# BasicPeripherals.net
KiCad netlist of a schematic drawn in Altium Designer
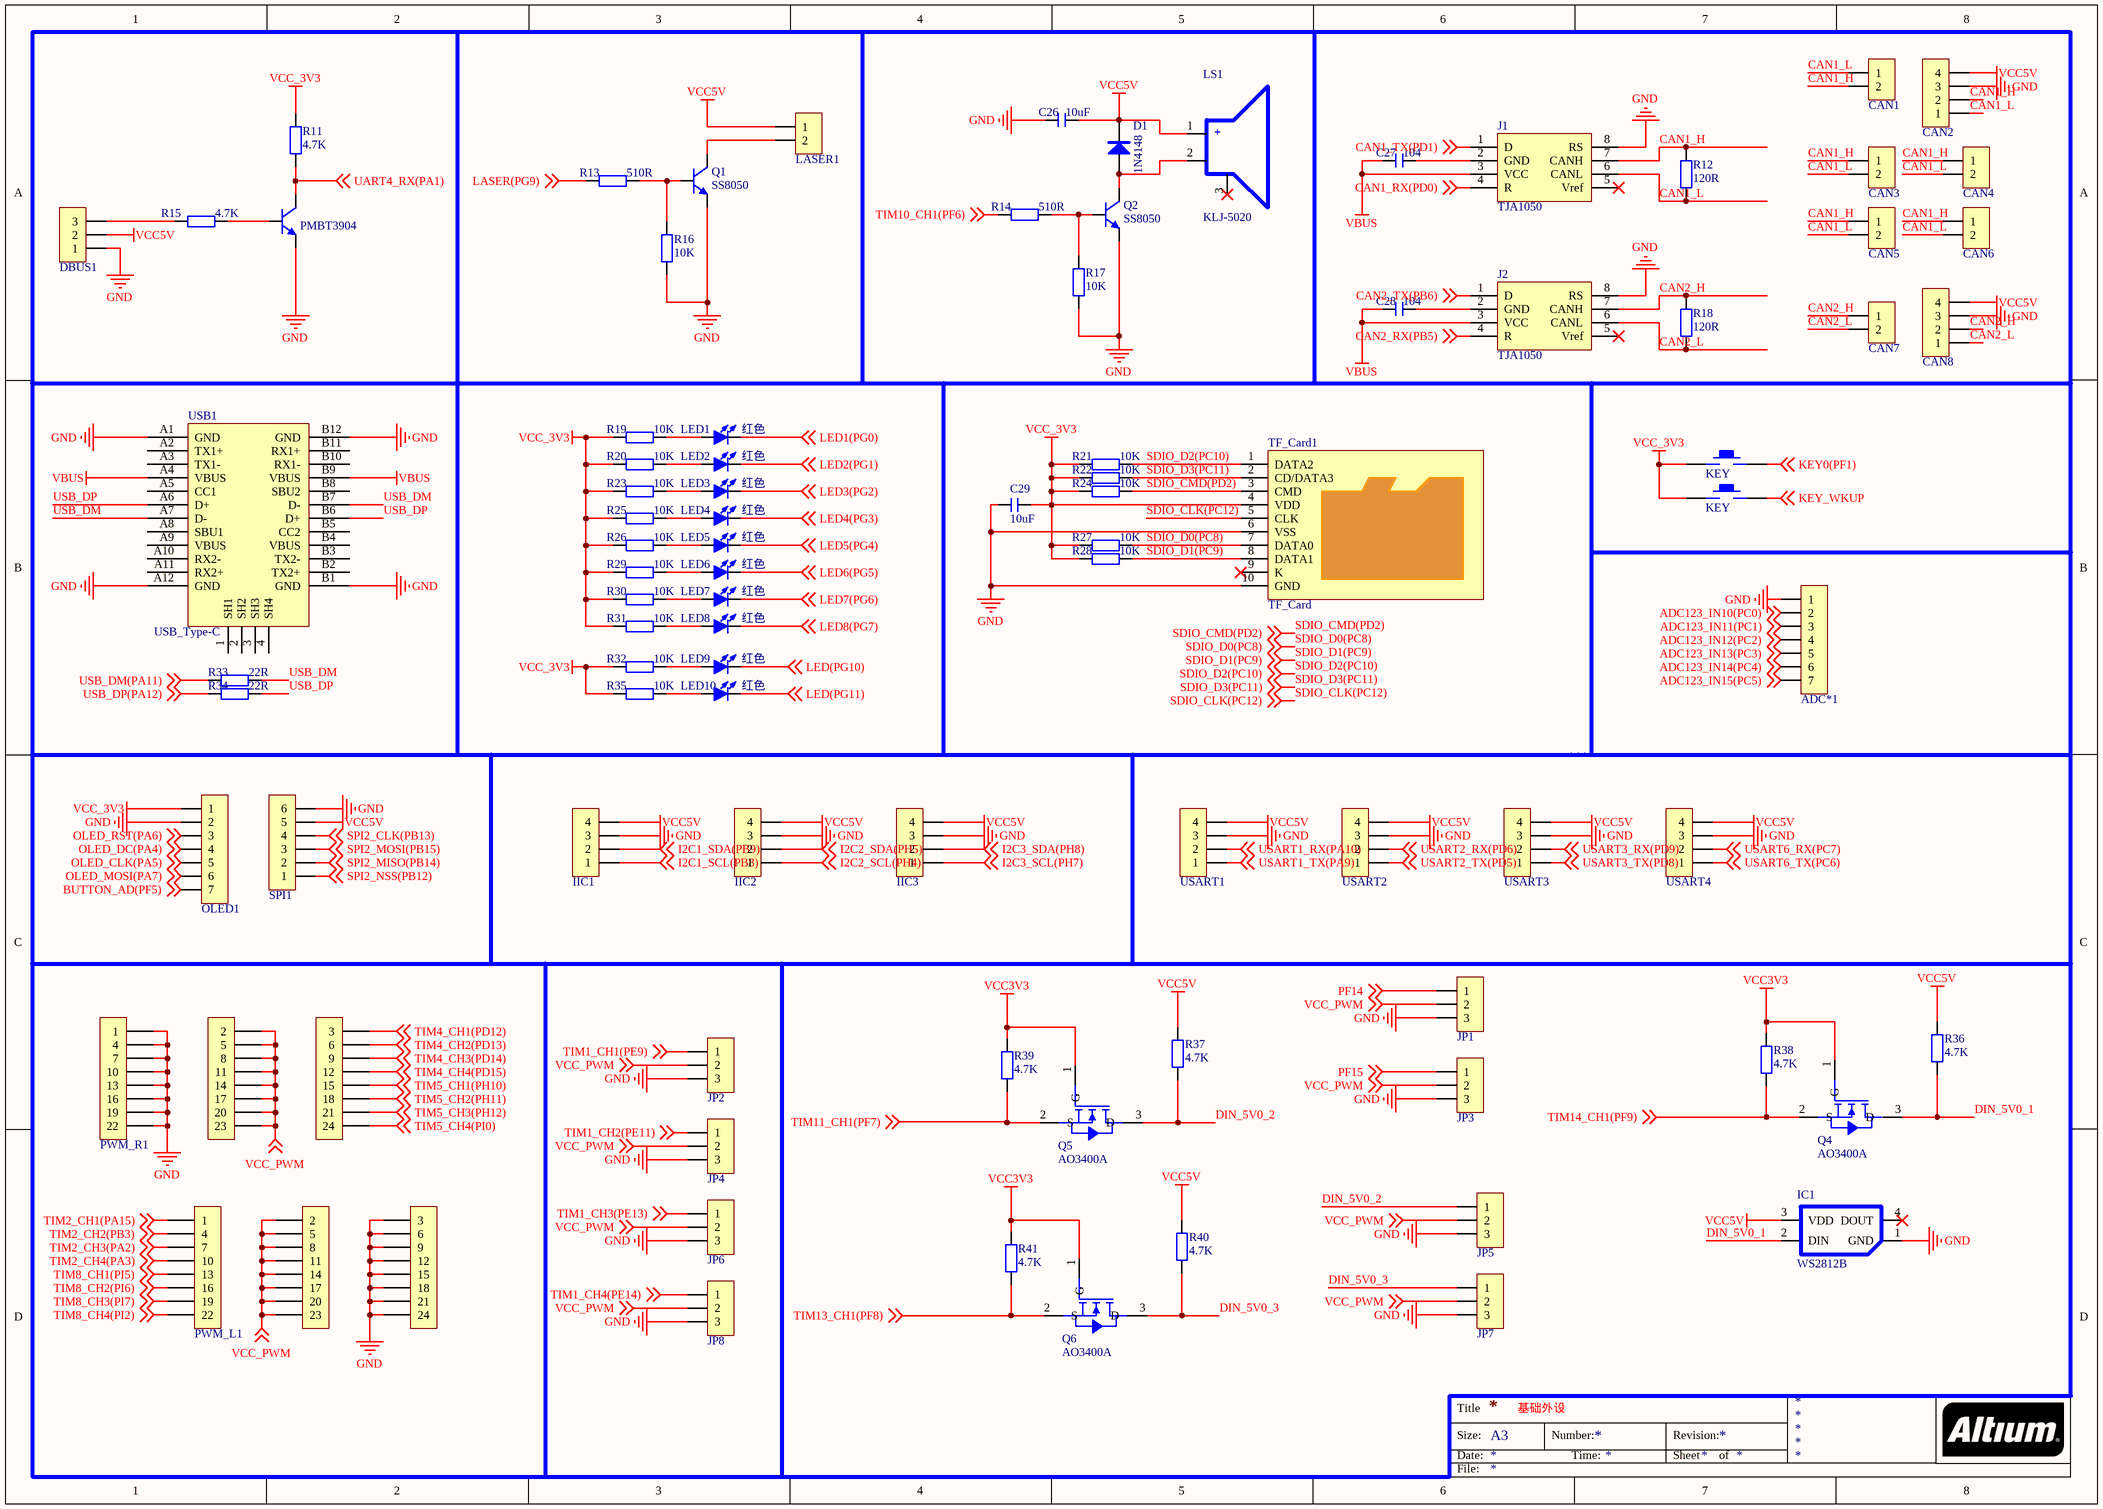
[diagram p0: BasicPeripherals.SchDoc]

(export (version "E")
  (design (tool "Eeschema 10.0.6"))
  (components
    (comp (ref "ADC*1")
      (value "HDR-1X7")
      (footprint "MX 1.25-WS-7P")
      (description "7P接插件")
      (libsource (lib "5.0 - 接插件-脚距1.25") (part "Header 7"))
    )
    (comp (ref "C26")
      (value "10uF")
      (footprint "C 0402_M")
      (description "贴片电容")
      (libsource (lib "0.1 - 电阻-电容-电感") (part "C"))
    )
    (comp (ref "C27")
      (value "104")
      (footprint "C 0603_L")
      (description "贴片电容")
      (libsource (lib "0.1 - 电阻-电容-电感") (part "C"))
    )
    (comp (ref "C28")
      (value "104")
      (footprint "C 0603_L")
      (description "贴片电容")
      (libsource (lib "0.1 - 电阻-电容-电感") (part "C"))
    )
    (comp (ref "C29")
      (value "10uF")
      (footprint "C 0402_M")
      (description "贴片电容")
      (libsource (lib "0.1 - 电阻-电容-电感") (part "C"))
    )
    (comp (ref "CAN1")
      (value "HDR-1X2")
      (footprint "MX 1.25-WS-2P")
      (description "2P接插件")
      (libsource (lib "5.0 - 接插件-脚距1.25") (part "Header 2"))
    )
    (comp (ref "CAN2")
      (value "HDR-1X4")
      (footprint "MX 1.25-WS-4P")
      (description "4P接插件")
      (libsource (lib "5.0 - 接插件-脚距1.25") (part "Header 4"))
    )
    (comp (ref "CAN3")
      (value "HDR-1X2")
      (footprint "MX 1.25-LS-2P")
      (description "2P接插件")
      (libsource (lib "5.0 - 接插件-脚距1.25") (part "Header 2"))
    )
    (comp (ref "CAN4")
      (value "HDR-1X2")
      (footprint "MX 1.25-LS-2P")
      (description "2P接插件")
      (libsource (lib "5.0 - 接插件-脚距1.25") (part "Header 2"))
    )
    (comp (ref "CAN5")
      (value "HDR-1X2")
      (footprint "MX 1.25-LS-2P")
      (description "2P接插件")
      (libsource (lib "5.0 - 接插件-脚距1.25") (part "Header 2"))
    )
    (comp (ref "CAN6")
      (value "HDR-1X2")
      (footprint "MX 1.25-LS-2P")
      (description "2P接插件")
      (libsource (lib "5.0 - 接插件-脚距1.25") (part "Header 2"))
    )
    (comp (ref "CAN7")
      (value "HDR-1X2")
      (footprint "MX 1.25-LS-2P")
      (description "2P接插件")
      (libsource (lib "5.0 - 接插件-脚距1.25") (part "Header 2"))
    )
    (comp (ref "CAN8")
      (value "HDR-1X4")
      (footprint "MX 1.25-LS-4P")
      (description "4P接插件")
      (libsource (lib "5.0 - 接插件-脚距1.25") (part "Header 4"))
    )
    (comp (ref "D1")
      (value "1N4148")
      (footprint "SOD-323")
      (description "开关二极管")
      (libsource (lib "0.2 -  二极管-整流桥") (part "1N4148"))
    )
    (comp (ref "DBUS1")
      (value "HDR-1X3")
      (footprint "HDR2.54-WS-3P")
      (description "3P接插件")
      (libsource (lib "") (part "Header 3_1"))
    )
    (comp (ref "IC1")
      (value "WS2812B")
      (footprint "LED 3528-4Pin")
      (libsource (lib "mx_pcb_library") (part "WS2812B"))
    )
    (comp (ref "IIC1")
      (value "HDR-1X4")
      (footprint "MX 1.25-LS-4P")
      (description "4P接插件")
      (libsource (lib "5.0 - 接插件-脚距1.25") (part "Header 4"))
    )
    (comp (ref "IIC2")
      (value "HDR-1X4")
      (footprint "MX 1.25-LS-4P")
      (description "4P接插件")
      (libsource (lib "5.0 - 接插件-脚距1.25") (part "Header 4"))
    )
    (comp (ref "IIC3")
      (value "HDR-1X4")
      (footprint "MX 1.25-LS-4P")
      (description "4P接插件")
      (libsource (lib "5.0 - 接插件-脚距1.25") (part "Header 4"))
    )
    (comp (ref "J1")
      (value "TJA1050")
      (footprint "mx_pcb_library:SOIC-8_150mil")
      (description "CAN芯片")
      (libsource (lib "mx_pcb_library") (part "TJA1050"))
    )
    (comp (ref "J2")
      (value "TJA1050")
      (footprint "mx_pcb_library:SOIC-8_150mil")
      (description "CAN芯片")
      (libsource (lib "mx_pcb_library") (part "TJA1050"))
    )
    (comp (ref "JP1")
      (value "HDR-1X3")
      (footprint "HDR2.54-LI-3P")
      (description "3P接插件")
      (libsource (lib "5.3 - 接插件-脚距2.54 (100mil) ") (part "Header 3"))
    )
    (comp (ref "JP2")
      (value "HDR-1X3")
      (footprint "HDR2.54-LI-3P")
      (description "3P接插件")
      (libsource (lib "5.3 - 接插件-脚距2.54 (100mil) ") (part "Header 3"))
    )
    (comp (ref "JP3")
      (value "HDR-1X3")
      (footprint "HDR2.54-LI-3P")
      (description "3P接插件")
      (libsource (lib "5.3 - 接插件-脚距2.54 (100mil) ") (part "Header 3"))
    )
    (comp (ref "JP4")
      (value "HDR-1X3")
      (footprint "HDR2.54-LI-3P")
      (description "3P接插件")
      (libsource (lib "5.3 - 接插件-脚距2.54 (100mil) ") (part "Header 3"))
    )
    (comp (ref "JP5")
      (value "HDR-1X3")
      (footprint "HDR2.54-LI-3P")
      (description "3P接插件")
      (libsource (lib "5.3 - 接插件-脚距2.54 (100mil) ") (part "Header 3"))
    )
    (comp (ref "JP6")
      (value "HDR-1X3")
      (footprint "HDR2.54-LI-3P")
      (description "3P接插件")
      (libsource (lib "5.3 - 接插件-脚距2.54 (100mil) ") (part "Header 3"))
    )
    (comp (ref "JP7")
      (value "HDR-1X3")
      (footprint "HDR2.54-LI-3P")
      (description "3P接插件")
      (libsource (lib "5.3 - 接插件-脚距2.54 (100mil) ") (part "Header 3"))
    )
    (comp (ref "JP8")
      (value "HDR-1X3")
      (footprint "HDR2.54-LI-3P")
      (description "3P接插件")
      (libsource (lib "5.3 - 接插件-脚距2.54 (100mil) ") (part "Header 3"))
    )
    (comp (ref "LASER1")
      (value "HDR-1X2")
      (footprint "MX 1.25-LS-2P")
      (description "2P接插件")
      (libsource (lib "5.0 - 接插件-脚距1.25") (part "Header 2"))
    )
    (comp (ref "LED1")
      (value "红色")
      (footprint "LED 0805G")
      (description "贴片LED")
      (libsource (lib "0.3 - LED发光二极管") (part "LED-SMD"))
    )
    (comp (ref "LED2")
      (value "红色")
      (footprint "LED 0805G")
      (description "贴片LED")
      (libsource (lib "0.3 - LED发光二极管") (part "LED-SMD"))
    )
    (comp (ref "LED3")
      (value "红色")
      (footprint "LED 0805G")
      (description "贴片LED")
      (libsource (lib "0.3 - LED发光二极管") (part "LED-SMD"))
    )
    (comp (ref "LED4")
      (value "红色")
      (footprint "LED 0805G")
      (description "贴片LED")
      (libsource (lib "0.3 - LED发光二极管") (part "LED-SMD"))
    )
    (comp (ref "LED5")
      (value "红色")
      (footprint "LED 0805G")
      (description "贴片LED")
      (libsource (lib "0.3 - LED发光二极管") (part "LED-SMD"))
    )
    (comp (ref "LED6")
      (value "红色")
      (footprint "LED 0805G")
      (description "贴片LED")
      (libsource (lib "0.3 - LED发光二极管") (part "LED-SMD"))
    )
    (comp (ref "LED7")
      (value "红色")
      (footprint "LED 0805G")
      (description "贴片LED")
      (libsource (lib "0.3 - LED发光二极管") (part "LED-SMD"))
    )
    (comp (ref "LED8")
      (value "红色")
      (footprint "LED 0805G")
      (description "贴片LED")
      (libsource (lib "0.3 - LED发光二极管") (part "LED-SMD"))
    )
    (comp (ref "LED9")
      (value "红色")
      (footprint "LED 0805R")
      (description "贴片LED")
      (libsource (lib "0.3 - LED发光二极管") (part "LED-SMD"))
    )
    (comp (ref "LED10")
      (value "红色")
      (footprint "LED 0805R")
      (description "贴片LED")
      (libsource (lib "0.3 - LED发光二极管") (part "LED-SMD"))
    )
    (comp (ref "LS1")
      (value "KLJ-5020")
      (footprint "mx_pcb_library:BUZ-SMD_4P-L5.0-W5.0-P3.80-TL")
      (description "蜂鸣器")
      (libsource (lib "mx_pcb_library") (part "KLJ-5020"))
    )
    (comp (ref "OLED1")
      (value "HDR-1X7")
      (footprint "MX 1.25-WS-7P")
      (description "7P接插件")
      (libsource (lib "5.0 - 接插件-脚距1.25") (part "Header 7"))
    )
    (comp (ref "PWM_L1")
      (value "HDR3*8-left")
      (footprint "mx_pcb_library:PIN-3*8-2.54 - duplicate")
      (description "Connector")
      (libsource (lib "mx_pcb_library") (part "HDR3*8-left"))
    )
    (comp (ref "PWM_R1")
      (value "HDR3*8-right")
      (footprint "mx_pcb_library:PIN-3*8-2.54 - duplicate")
      (description "Connector")
      (libsource (lib "mx_pcb_library") (part "HDR3*8-right"))
    )
    (comp (ref "Q1")
      (value "SS8050")
      (footprint "SOT23-3L")
      (description "高频放大-NPN型")
      (libsource (lib "0.4 - 三极管") (part "8050-SMD"))
    )
    (comp (ref "Q2")
      (value "SS8050")
      (footprint "SOT23-3L")
      (description "高频放大-NPN型")
      (libsource (lib "0.4 - 三极管") (part "8050-SMD"))
    )
    (comp (ref "Q3")
      (value "PMBT3904")
      (footprint "mx_pcb_library:SOT-23-3")
      (description "NPN Bipolar Transistor")
      (libsource (lib "mx_pcb_library") (part "PMBT3904"))
    )
    (comp (ref "Q4")
      (value "AO3400A")
      (footprint "mx_pcb_library:SOT-23-3_L2.9-W1.3-P1.90-LS2.4-BR")
      (libsource (lib "mx_pcb_library") (part "AO3400A"))
    )
    (comp (ref "Q5")
      (value "AO3400A")
      (footprint "mx_pcb_library:SOT-23-3_L2.9-W1.3-P1.90-LS2.4-BR")
      (libsource (lib "mx_pcb_library") (part "AO3400A"))
    )
    (comp (ref "Q6")
      (value "AO3400A")
      (footprint "mx_pcb_library:SOT-23-3_L2.9-W1.3-P1.90-LS2.4-BR")
      (libsource (lib "mx_pcb_library") (part "AO3400A"))
    )
    (comp (ref "R11")
      (value "4.7K")
      (footprint "R 0402_M")
      (description "贴片电阻")
      (libsource (lib "0.1 - 电阻-电容-电感") (part "R"))
    )
    (comp (ref "R12")
      (value "120R")
      (footprint "R 0402_M")
      (description "贴片电阻")
      (libsource (lib "0.1 - 电阻-电容-电感") (part "R"))
    )
    (comp (ref "R13")
      (value "510R")
      (footprint "R 0402_M")
      (description "贴片电阻")
      (libsource (lib "0.1 - 电阻-电容-电感") (part "R"))
    )
    (comp (ref "R14")
      (value "510R")
      (footprint "R 0402_M")
      (description "贴片电阻")
      (libsource (lib "0.1 - 电阻-电容-电感") (part "R"))
    )
    (comp (ref "R15")
      (value "4.7K")
      (footprint "R 0402_M")
      (description "贴片电阻")
      (libsource (lib "0.1 - 电阻-电容-电感") (part "R"))
    )
    (comp (ref "R16")
      (value "10K")
      (footprint "R 0402_M")
      (description "贴片电阻")
      (libsource (lib "0.1 - 电阻-电容-电感") (part "R"))
    )
    (comp (ref "R17")
      (value "10K")
      (footprint "R 0402_M")
      (description "贴片电阻")
      (libsource (lib "0.1 - 电阻-电容-电感") (part "R"))
    )
    (comp (ref "R18")
      (value "120R")
      (footprint "R 0402_M")
      (description "贴片电阻")
      (libsource (lib "0.1 - 电阻-电容-电感") (part "R"))
    )
    (comp (ref "R19")
      (value "10K")
      (footprint "R 0402_M")
      (description "贴片电阻")
      (libsource (lib "0.1 - 电阻-电容-电感") (part "R"))
    )
    (comp (ref "R20")
      (value "10K")
      (footprint "R 0402_M")
      (description "贴片电阻")
      (libsource (lib "0.1 - 电阻-电容-电感") (part "R"))
    )
    (comp (ref "R21")
      (value "10K")
      (footprint "R 0402_M")
      (description "贴片电阻")
      (libsource (lib "0.1 - 电阻-电容-电感") (part "R"))
    )
    (comp (ref "R22")
      (value "10K")
      (footprint "R 0402_M")
      (description "贴片电阻")
      (libsource (lib "0.1 - 电阻-电容-电感") (part "R"))
    )
    (comp (ref "R23")
      (value "10K")
      (footprint "R 0402_M")
      (description "贴片电阻")
      (libsource (lib "0.1 - 电阻-电容-电感") (part "R"))
    )
    (comp (ref "R24")
      (value "10K")
      (footprint "R 0402_M")
      (description "贴片电阻")
      (libsource (lib "0.1 - 电阻-电容-电感") (part "R"))
    )
    (comp (ref "R25")
      (value "10K")
      (footprint "R 0402_M")
      (description "贴片电阻")
      (libsource (lib "0.1 - 电阻-电容-电感") (part "R"))
    )
    (comp (ref "R26")
      (value "10K")
      (footprint "R 0402_M")
      (description "贴片电阻")
      (libsource (lib "0.1 - 电阻-电容-电感") (part "R"))
    )
    (comp (ref "R27")
      (value "10K")
      (footprint "R 0402_M")
      (description "贴片电阻")
      (libsource (lib "0.1 - 电阻-电容-电感") (part "R"))
    )
    (comp (ref "R28")
      (value "10K")
      (footprint "R 0402_M")
      (description "贴片电阻")
      (libsource (lib "0.1 - 电阻-电容-电感") (part "R"))
    )
    (comp (ref "R29")
      (value "10K")
      (footprint "R 0402_M")
      (description "贴片电阻")
      (libsource (lib "0.1 - 电阻-电容-电感") (part "R"))
    )
    (comp (ref "R30")
      (value "10K")
      (footprint "R 0402_M")
      (description "贴片电阻")
      (libsource (lib "0.1 - 电阻-电容-电感") (part "R"))
    )
    (comp (ref "R31")
      (value "10K")
      (footprint "R 0402_M")
      (description "贴片电阻")
      (libsource (lib "0.1 - 电阻-电容-电感") (part "R"))
    )
    (comp (ref "R32")
      (value "10K")
      (footprint "R 0402_M")
      (description "贴片电阻")
      (libsource (lib "0.1 - 电阻-电容-电感") (part "R"))
    )
    (comp (ref "R33")
      (value "22R")
      (footprint "R 0402_M")
      (description "贴片电阻")
      (libsource (lib "0.1 - 电阻-电容-电感") (part "R"))
    )
    (comp (ref "R34")
      (value "22R")
      (footprint "R 0402_M")
      (description "贴片电阻")
      (libsource (lib "0.1 - 电阻-电容-电感") (part "R"))
    )
    (comp (ref "R35")
      (value "10K")
      (footprint "R 0402_M")
      (description "贴片电阻")
      (libsource (lib "0.1 - 电阻-电容-电感") (part "R"))
    )
    (comp (ref "R36")
      (value "4.7K")
      (footprint "R 0402_M")
      (description "贴片电阻")
      (libsource (lib "0.1 - 电阻-电容-电感") (part "R"))
    )
    (comp (ref "R37")
      (value "4.7K")
      (footprint "R 0402_M")
      (description "贴片电阻")
      (libsource (lib "0.1 - 电阻-电容-电感") (part "R"))
    )
    (comp (ref "R38")
      (value "4.7K")
      (footprint "R 0402_M")
      (description "贴片电阻")
      (libsource (lib "0.1 - 电阻-电容-电感") (part "R"))
    )
    (comp (ref "R39")
      (value "4.7K")
      (footprint "R 0402_M")
      (description "贴片电阻")
      (libsource (lib "0.1 - 电阻-电容-电感") (part "R"))
    )
    (comp (ref "R40")
      (value "4.7K")
      (footprint "R 0402_M")
      (description "贴片电阻")
      (libsource (lib "0.1 - 电阻-电容-电感") (part "R"))
    )
    (comp (ref "R41")
      (value "4.7K")
      (footprint "R 0402_M")
      (description "贴片电阻")
      (libsource (lib "0.1 - 电阻-电容-电感") (part "R"))
    )
    (comp (ref "RST2")
      (value "KEY")
      (footprint "mx_pcb_library:SMD-3.2*4.2")
      (libsource (lib "mx_pcb_library") (part "KEY_M"))
    )
    (comp (ref "RST3")
      (value "KEY")
      (footprint "mx_pcb_library:SMD-3.2*4.2")
      (libsource (lib "mx_pcb_library") (part "KEY_M"))
    )
    (comp (ref "SPI1")
      (value "HDR-1X6")
      (footprint "MX 1.25-LS-6P")
      (description "6P接插件")
      (libsource (lib "5.0 - 接插件-脚距1.25") (part "Header 6"))
    )
    (comp (ref "TF_Card1")
      (value "TF_Card")
      (footprint "Micro SD")
      (description "TF卡座")
      (libsource (lib "0.8 - 网口-音频插座") (part "TF_Card"))
    )
    (comp (ref "USART1")
      (value "HDR-1X4")
      (footprint "MX 1.25-LS-4P")
      (description "4P接插件")
      (libsource (lib "5.0 - 接插件-脚距1.25") (part "Header 4"))
    )
    (comp (ref "USART2")
      (value "HDR-1X4")
      (footprint "MX 1.25-LS-4P")
      (description "4P接插件")
      (libsource (lib "5.0 - 接插件-脚距1.25") (part "Header 4"))
    )
    (comp (ref "USART3")
      (value "HDR-1X4")
      (footprint "MX 1.25-LS-4P")
      (description "4P接插件")
      (libsource (lib "5.0 - 接插件-脚距1.25") (part "Header 4"))
    )
    (comp (ref "USART4")
      (value "HDR-1X4")
      (footprint "MX 1.25-LS-4P")
      (description "4P接插件")
      (libsource (lib "5.0 - 接插件-脚距1.25") (part "Header 4"))
    )
    (comp (ref "USB1")
      (value "USB_Type-C")
      (footprint "mx_pcb_library:Type-C-TOP")
      (libsource (lib "mx_pcb_library") (part "USB_Type-C"))
    )
  )
  (nets
    (net (code "1") (name "/CAN1_H") (class "Default")
      (node (ref "CAN1") (pin "2") (pinfunction "2_2") (pintype "passive"))
      (node (ref "CAN2") (pin "2") (pinfunction "2_2") (pintype "passive"))
      (node (ref "CAN3") (pin "1") (pinfunction "1_1") (pintype "passive"))
      (node (ref "CAN4") (pin "1") (pinfunction "1_1") (pintype "passive"))
      (node (ref "CAN5") (pin "1") (pinfunction "1_1") (pintype "passive"))
      (node (ref "CAN6") (pin "1") (pinfunction "1_1") (pintype "passive"))
      (node (ref "J1") (pin "7") (pinfunction "CANH_7") (pintype "passive"))
      (node (ref "R12") (pin "2") (pinfunction "2_2") (pintype "passive"))
    )
    (net (code "2") (name "/CAN1_L") (class "Default")
      (node (ref "CAN1") (pin "1") (pinfunction "1_1") (pintype "passive"))
      (node (ref "CAN2") (pin "1") (pinfunction "1_1") (pintype "passive"))
      (node (ref "CAN3") (pin "2") (pinfunction "2_2") (pintype "passive"))
      (node (ref "CAN4") (pin "2") (pinfunction "2_2") (pintype "passive"))
      (node (ref "CAN5") (pin "2") (pinfunction "2_2") (pintype "passive"))
      (node (ref "CAN6") (pin "2") (pinfunction "2_2") (pintype "passive"))
      (node (ref "J1") (pin "6") (pinfunction "CANL_6") (pintype "passive"))
      (node (ref "R12") (pin "1") (pinfunction "1_1") (pintype "passive"))
    )
    (net (code "3") (name "/CAN2_H") (class "Default")
      (node (ref "CAN7") (pin "1") (pinfunction "1_1") (pintype "passive"))
      (node (ref "CAN8") (pin "2") (pinfunction "2_2") (pintype "passive"))
      (node (ref "J2") (pin "7") (pinfunction "CANH_7") (pintype "passive"))
      (node (ref "R18") (pin "2") (pinfunction "2_2") (pintype "passive"))
    )
    (net (code "4") (name "/CAN2_L") (class "Default")
      (node (ref "CAN7") (pin "2") (pinfunction "2_2") (pintype "passive"))
      (node (ref "CAN8") (pin "1") (pinfunction "1_1") (pintype "passive"))
      (node (ref "J2") (pin "6") (pinfunction "CANL_6") (pintype "passive"))
      (node (ref "R18") (pin "1") (pinfunction "1_1") (pintype "passive"))
    )
    (net (code "5") (name "/DIN_5V0_1") (class "Default")
      (node (ref "IC1") (pin "2") (pinfunction "DIN_2") (pintype "passive"))
      (node (ref "Q4") (pin "3") (pinfunction "D_3") (pintype "passive"))
      (node (ref "R36") (pin "2") (pinfunction "2_2") (pintype "passive"))
    )
    (net (code "6") (name "/DIN_5V0_2") (class "Default")
      (node (ref "JP5") (pin "1") (pinfunction "1_1") (pintype "passive"))
      (node (ref "Q5") (pin "3") (pinfunction "D_3") (pintype "passive"))
      (node (ref "R37") (pin "2") (pinfunction "2_2") (pintype "passive"))
    )
    (net (code "7") (name "/DIN_5V0_3") (class "Default")
      (node (ref "JP7") (pin "1") (pinfunction "1_1") (pintype "passive"))
      (node (ref "Q6") (pin "3") (pinfunction "D_3") (pintype "passive"))
      (node (ref "R40") (pin "2") (pinfunction "2_2") (pintype "passive"))
    )
    (net (code "8") (name "/USB_DM") (class "Default")
      (node (ref "R33") (pin "2") (pinfunction "2_2") (pintype "passive"))
      (node (ref "USB1") (pin "A7") (pinfunction "D-_A7") (pintype "passive"))
      (node (ref "USB1") (pin "B7") (pinfunction "D-_B7") (pintype "passive"))
    )
    (net (code "9") (name "/USB_DP") (class "Default")
      (node (ref "R34") (pin "2") (pinfunction "2_2") (pintype "passive"))
      (node (ref "USB1") (pin "A6") (pinfunction "D+_A6") (pintype "passive"))
      (node (ref "USB1") (pin "B6") (pinfunction "D+_B6") (pintype "passive"))
    )
    (net (code "10") (name "ADC123_IN10(PC0)") (class "Default")
      (node (ref "ADC*1") (pin "2") (pinfunction "2_2") (pintype "passive"))
    )
    (net (code "11") (name "ADC123_IN11(PC1)") (class "Default")
      (node (ref "ADC*1") (pin "3") (pinfunction "3_3") (pintype "passive"))
    )
    (net (code "12") (name "ADC123_IN12(PC2)") (class "Default")
      (node (ref "ADC*1") (pin "4") (pinfunction "4_4") (pintype "passive"))
    )
    (net (code "13") (name "ADC123_IN13(PC3)") (class "Default")
      (node (ref "ADC*1") (pin "5") (pinfunction "5_5") (pintype "passive"))
    )
    (net (code "14") (name "ADC123_IN14(PC4)") (class "Default")
      (node (ref "ADC*1") (pin "6") (pinfunction "6_6") (pintype "passive"))
    )
    (net (code "15") (name "ADC123_IN15(PC5)") (class "Default")
      (node (ref "ADC*1") (pin "7") (pinfunction "7_7") (pintype "passive"))
    )
    (net (code "16") (name "BUTTON_AD(PF5)") (class "Default")
      (node (ref "OLED1") (pin "7") (pinfunction "7_7") (pintype "passive"))
    )
    (net (code "17") (name "CAN1_RX(PD0)") (class "Default")
      (node (ref "J1") (pin "4") (pinfunction "R_4") (pintype "passive"))
    )
    (net (code "18") (name "CAN1_TX(PD1)") (class "Default")
      (node (ref "J1") (pin "1") (pinfunction "D_1") (pintype "passive"))
    )
    (net (code "19") (name "CAN2_RX(PB5)") (class "Default")
      (node (ref "J2") (pin "4") (pinfunction "R_4") (pintype "passive"))
    )
    (net (code "20") (name "CAN2_TX(PB6)") (class "Default")
      (node (ref "J2") (pin "1") (pinfunction "D_1") (pintype "passive"))
    )
    (net (code "21") (name "GND") (class "Default")
      (node (ref "ADC*1") (pin "1") (pinfunction "1_1") (pintype "passive"))
      (node (ref "C26") (pin "2") (pinfunction "2_2") (pintype "passive"))
      (node (ref "C29") (pin "1") (pinfunction "1_1") (pintype "passive"))
      (node (ref "CAN2") (pin "3") (pinfunction "3_3") (pintype "passive"))
      (node (ref "CAN8") (pin "3") (pinfunction "3_3") (pintype "passive"))
      (node (ref "DBUS1") (pin "1") (pinfunction "1_1") (pintype "passive"))
      (node (ref "IC1") (pin "1") (pinfunction "GND_1") (pintype "passive"))
      (node (ref "IIC1") (pin "3") (pinfunction "3_3") (pintype "passive"))
      (node (ref "IIC2") (pin "3") (pinfunction "3_3") (pintype "passive"))
      (node (ref "IIC3") (pin "3") (pinfunction "3_3") (pintype "passive"))
      (node (ref "J1") (pin "8") (pinfunction "RS_8") (pintype "passive"))
      (node (ref "J2") (pin "8") (pinfunction "RS_8") (pintype "passive"))
      (node (ref "JP1") (pin "3") (pinfunction "3_3") (pintype "passive"))
      (node (ref "JP2") (pin "3") (pinfunction "3_3") (pintype "passive"))
      (node (ref "JP3") (pin "3") (pinfunction "3_3") (pintype "passive"))
      (node (ref "JP4") (pin "3") (pinfunction "3_3") (pintype "passive"))
      (node (ref "JP5") (pin "3") (pinfunction "3_3") (pintype "passive"))
      (node (ref "JP6") (pin "3") (pinfunction "3_3") (pintype "passive"))
      (node (ref "JP7") (pin "3") (pinfunction "3_3") (pintype "passive"))
      (node (ref "JP8") (pin "3") (pinfunction "3_3") (pintype "passive"))
      (node (ref "OLED1") (pin "2") (pinfunction "2_2") (pintype "passive"))
      (node (ref "PWM_L1") (pin "12") (pinfunction "12_12") (pintype "passive"))
      (node (ref "PWM_L1") (pin "15") (pinfunction "15_15") (pintype "passive"))
      (node (ref "PWM_L1") (pin "18") (pinfunction "18_18") (pintype "passive"))
      (node (ref "PWM_L1") (pin "21") (pinfunction "21_21") (pintype "passive"))
      (node (ref "PWM_L1") (pin "24") (pinfunction "24_24") (pintype "passive"))
      (node (ref "PWM_L1") (pin "3") (pinfunction "3_3") (pintype "passive"))
      (node (ref "PWM_L1") (pin "6") (pinfunction "6_6") (pintype "passive"))
      (node (ref "PWM_L1") (pin "9") (pinfunction "9_9") (pintype "passive"))
      (node (ref "PWM_R1") (pin "1") (pinfunction "1_1") (pintype "passive"))
      (node (ref "PWM_R1") (pin "10") (pinfunction "10_10") (pintype "passive"))
      (node (ref "PWM_R1") (pin "13") (pinfunction "13_13") (pintype "passive"))
      (node (ref "PWM_R1") (pin "16") (pinfunction "16_16") (pintype "passive"))
      (node (ref "PWM_R1") (pin "19") (pinfunction "19_19") (pintype "passive"))
      (node (ref "PWM_R1") (pin "22") (pinfunction "22_22") (pintype "passive"))
      (node (ref "PWM_R1") (pin "4") (pinfunction "4_4") (pintype "passive"))
      (node (ref "PWM_R1") (pin "7") (pinfunction "7_7") (pintype "passive"))
      (node (ref "Q1") (pin "2") (pinfunction "E_2") (pintype "passive"))
      (node (ref "Q2") (pin "2") (pinfunction "E_2") (pintype "passive"))
      (node (ref "Q3") (pin "2") (pinfunction "E_2") (pintype "passive"))
      (node (ref "R16") (pin "1") (pinfunction "1_1") (pintype "passive"))
      (node (ref "R17") (pin "1") (pinfunction "1_1") (pintype "passive"))
      (node (ref "SPI1") (pin "6") (pinfunction "6_6") (pintype "passive"))
      (node (ref "TF_Card1") (pin "10") (pinfunction "GND_10") (pintype "passive"))
      (node (ref "TF_Card1") (pin "6") (pinfunction "VSS_6") (pintype "passive"))
      (node (ref "USART1") (pin "3") (pinfunction "3_3") (pintype "passive"))
      (node (ref "USART2") (pin "3") (pinfunction "3_3") (pintype "passive"))
      (node (ref "USART3") (pin "3") (pinfunction "3_3") (pintype "passive"))
      (node (ref "USART4") (pin "3") (pinfunction "3_3") (pintype "passive"))
      (node (ref "USB1") (pin "A1") (pinfunction "GND_A1") (pintype "passive"))
      (node (ref "USB1") (pin "A12") (pinfunction "GND_A12") (pintype "passive"))
      (node (ref "USB1") (pin "B1") (pinfunction "GND_B1") (pintype "passive"))
      (node (ref "USB1") (pin "B12") (pinfunction "GND_B12") (pintype "passive"))
    )
    (net (code "22") (name "I2C1_SCL(PB8)") (class "Default")
      (node (ref "IIC1") (pin "1") (pinfunction "1_1") (pintype "passive"))
    )
    (net (code "23") (name "I2C1_SDA(PB9)") (class "Default")
      (node (ref "IIC1") (pin "2") (pinfunction "2_2") (pintype "passive"))
    )
    (net (code "24") (name "I2C2_SCL(PH4)") (class "Default")
      (node (ref "IIC2") (pin "1") (pinfunction "1_1") (pintype "passive"))
    )
    (net (code "25") (name "I2C2_SDA(PH5)") (class "Default")
      (node (ref "IIC2") (pin "2") (pinfunction "2_2") (pintype "passive"))
    )
    (net (code "26") (name "I2C3_SCL(PH7)") (class "Default")
      (node (ref "IIC3") (pin "1") (pinfunction "1_1") (pintype "passive"))
    )
    (net (code "27") (name "I2C3_SDA(PH8)") (class "Default")
      (node (ref "IIC3") (pin "2") (pinfunction "2_2") (pintype "passive"))
    )
    (net (code "28") (name "KEY0(PF1)") (class "Default")
      (node (ref "RST2") (pin "2") (pinfunction "2_2") (pintype "passive"))
    )
    (net (code "29") (name "KEY_WKUP") (class "Default")
      (node (ref "RST3") (pin "2") (pinfunction "2_2") (pintype "passive"))
    )
    (net (code "30") (name "LASER(PG9)") (class "Default")
      (node (ref "R13") (pin "1") (pinfunction "1_1") (pintype "passive"))
    )
    (net (code "31") (name "LED(PG10)") (class "Default")
      (node (ref "LED9") (pin "2") (pinfunction "K_2") (pintype "passive"))
    )
    (net (code "32") (name "LED(PG11)") (class "Default")
      (node (ref "LED10") (pin "2") (pinfunction "K_2") (pintype "passive"))
    )
    (net (code "33") (name "LED1(PG0)") (class "Default")
      (node (ref "LED1") (pin "2") (pinfunction "K_2") (pintype "passive"))
    )
    (net (code "34") (name "LED2(PG1)") (class "Default")
      (node (ref "LED2") (pin "2") (pinfunction "K_2") (pintype "passive"))
    )
    (net (code "35") (name "LED3(PG2)") (class "Default")
      (node (ref "LED3") (pin "2") (pinfunction "K_2") (pintype "passive"))
    )
    (net (code "36") (name "LED4(PG3)") (class "Default")
      (node (ref "LED4") (pin "2") (pinfunction "K_2") (pintype "passive"))
    )
    (net (code "37") (name "LED5(PG4)") (class "Default")
      (node (ref "LED5") (pin "2") (pinfunction "K_2") (pintype "passive"))
    )
    (net (code "38") (name "LED6(PG5)") (class "Default")
      (node (ref "LED6") (pin "2") (pinfunction "K_2") (pintype "passive"))
    )
    (net (code "39") (name "LED7(PG6)") (class "Default")
      (node (ref "LED7") (pin "2") (pinfunction "K_2") (pintype "passive"))
    )
    (net (code "40") (name "LED8(PG7)") (class "Default")
      (node (ref "LED8") (pin "2") (pinfunction "K_2") (pintype "passive"))
    )
    (net (code "41") (name "Net-(D1-A)") (class "Default")
      (node (ref "D1") (pin "1") (pinfunction "A_1") (pintype "passive"))
      (node (ref "LS1") (pin "2") (pinfunction "2_2") (pintype "passive"))
      (node (ref "Q2") (pin "3") (pinfunction "C_3") (pintype "passive"))
    )
    (net (code "42") (name "Net-(DBUS1-Pad3)") (class "Default")
      (node (ref "DBUS1") (pin "3") (pinfunction "3_3") (pintype "passive"))
      (node (ref "R15") (pin "2") (pinfunction "2_2") (pintype "passive"))
    )
    (net (code "43") (name "Net-(J1-GND)") (class "Default")
      (node (ref "C27") (pin "1") (pinfunction "1_1") (pintype "passive"))
      (node (ref "J1") (pin "2") (pinfunction "GND_2") (pintype "passive"))
    )
    (net (code "44") (name "Net-(J2-GND)") (class "Default")
      (node (ref "C28") (pin "1") (pinfunction "1_1") (pintype "passive"))
      (node (ref "J2") (pin "2") (pinfunction "GND_2") (pintype "passive"))
    )
    (net (code "45") (name "Net-(LED1-A)") (class "Default")
      (node (ref "LED1") (pin "1") (pinfunction "A_1") (pintype "passive"))
      (node (ref "R19") (pin "2") (pinfunction "2_2") (pintype "passive"))
    )
    (net (code "46") (name "Net-(LED2-A)") (class "Default")
      (node (ref "LED2") (pin "1") (pinfunction "A_1") (pintype "passive"))
      (node (ref "R20") (pin "2") (pinfunction "2_2") (pintype "passive"))
    )
    (net (code "47") (name "Net-(LED3-A)") (class "Default")
      (node (ref "LED3") (pin "1") (pinfunction "A_1") (pintype "passive"))
      (node (ref "R23") (pin "2") (pinfunction "2_2") (pintype "passive"))
    )
    (net (code "48") (name "Net-(LED4-A)") (class "Default")
      (node (ref "LED4") (pin "1") (pinfunction "A_1") (pintype "passive"))
      (node (ref "R25") (pin "2") (pinfunction "2_2") (pintype "passive"))
    )
    (net (code "49") (name "Net-(LED5-A)") (class "Default")
      (node (ref "LED5") (pin "1") (pinfunction "A_1") (pintype "passive"))
      (node (ref "R26") (pin "2") (pinfunction "2_2") (pintype "passive"))
    )
    (net (code "50") (name "Net-(LED6-A)") (class "Default")
      (node (ref "LED6") (pin "1") (pinfunction "A_1") (pintype "passive"))
      (node (ref "R29") (pin "2") (pinfunction "2_2") (pintype "passive"))
    )
    (net (code "51") (name "Net-(LED7-A)") (class "Default")
      (node (ref "LED7") (pin "1") (pinfunction "A_1") (pintype "passive"))
      (node (ref "R30") (pin "2") (pinfunction "2_2") (pintype "passive"))
    )
    (net (code "52") (name "Net-(LED8-A)") (class "Default")
      (node (ref "LED8") (pin "1") (pinfunction "A_1") (pintype "passive"))
      (node (ref "R31") (pin "2") (pinfunction "2_2") (pintype "passive"))
    )
    (net (code "53") (name "Net-(LED9-A)") (class "Default")
      (node (ref "LED9") (pin "1") (pinfunction "A_1") (pintype "passive"))
      (node (ref "R32") (pin "2") (pinfunction "2_2") (pintype "passive"))
    )
    (net (code "54") (name "Net-(LED10-A)") (class "Default")
      (node (ref "LED10") (pin "1") (pinfunction "A_1") (pintype "passive"))
      (node (ref "R35") (pin "2") (pinfunction "2_2") (pintype "passive"))
    )
    (net (code "55") (name "Net-(Q1-B)") (class "Default")
      (node (ref "Q1") (pin "1") (pinfunction "B_1") (pintype "passive"))
      (node (ref "R13") (pin "2") (pinfunction "2_2") (pintype "passive"))
      (node (ref "R16") (pin "2") (pinfunction "2_2") (pintype "passive"))
    )
    (net (code "56") (name "Net-(Q1-C)") (class "Default")
      (node (ref "LASER1") (pin "2") (pinfunction "2_2") (pintype "passive"))
      (node (ref "Q1") (pin "3") (pinfunction "C_3") (pintype "passive"))
    )
    (net (code "57") (name "Net-(Q2-B)") (class "Default")
      (node (ref "Q2") (pin "1") (pinfunction "B_1") (pintype "passive"))
      (node (ref "R14") (pin "2") (pinfunction "2_2") (pintype "passive"))
      (node (ref "R17") (pin "2") (pinfunction "2_2") (pintype "passive"))
    )
    (net (code "58") (name "Net-(Q3-B)") (class "Default")
      (node (ref "Q3") (pin "1") (pinfunction "B_1") (pintype "passive"))
      (node (ref "R15") (pin "1") (pinfunction "1_1") (pintype "passive"))
    )
    (net (code "59") (name "OLED_CLK(PA5)") (class "Default")
      (node (ref "OLED1") (pin "5") (pinfunction "5_5") (pintype "passive"))
    )
    (net (code "60") (name "OLED_DC(PA4)") (class "Default")
      (node (ref "OLED1") (pin "4") (pinfunction "4_4") (pintype "passive"))
    )
    (net (code "61") (name "OLED_MOSI(PA7)") (class "Default")
      (node (ref "OLED1") (pin "6") (pinfunction "6_6") (pintype "passive"))
    )
    (net (code "62") (name "OLED_RST(PA6)") (class "Default")
      (node (ref "OLED1") (pin "3") (pinfunction "3_3") (pintype "passive"))
    )
    (net (code "63") (name "PF14") (class "Default")
      (node (ref "JP1") (pin "1") (pinfunction "1_1") (pintype "passive"))
    )
    (net (code "64") (name "PF15") (class "Default")
      (node (ref "JP3") (pin "1") (pinfunction "1_1") (pintype "passive"))
    )
    (net (code "65") (name "SDIO_CLK(PC12)") (class "Default")
      (node (ref "TF_Card1") (pin "5") (pinfunction "CLK_5") (pintype "passive"))
    )
    (net (code "66") (name "SDIO_CMD(PD2)") (class "Default")
      (node (ref "R24") (pin "2") (pinfunction "2_2") (pintype "passive"))
      (node (ref "TF_Card1") (pin "3") (pinfunction "CMD_3") (pintype "passive"))
    )
    (net (code "67") (name "SDIO_D0(PC8)") (class "Default")
      (node (ref "R27") (pin "2") (pinfunction "2_2") (pintype "passive"))
      (node (ref "TF_Card1") (pin "7") (pinfunction "DATA0_7") (pintype "passive"))
    )
    (net (code "68") (name "SDIO_D1(PC9)") (class "Default")
      (node (ref "R28") (pin "2") (pinfunction "2_2") (pintype "passive"))
      (node (ref "TF_Card1") (pin "8") (pinfunction "DATA1_8") (pintype "passive"))
    )
    (net (code "69") (name "SDIO_D2(PC10)") (class "Default")
      (node (ref "R21") (pin "2") (pinfunction "2_2") (pintype "passive"))
      (node (ref "TF_Card1") (pin "1") (pinfunction "DATA2_1") (pintype "passive"))
    )
    (net (code "70") (name "SDIO_D3(PC11)") (class "Default")
      (node (ref "R22") (pin "2") (pinfunction "2_2") (pintype "passive"))
      (node (ref "TF_Card1") (pin "2") (pinfunction "CD/DATA3_2") (pintype "passive"))
    )
    (net (code "71") (name "SPI2_CLK(PB13)") (class "Default")
      (node (ref "SPI1") (pin "4") (pinfunction "4_4") (pintype "passive"))
    )
    (net (code "72") (name "SPI2_MISO(PB14)") (class "Default")
      (node (ref "SPI1") (pin "2") (pinfunction "2_2") (pintype "passive"))
    )
    (net (code "73") (name "SPI2_MOSI(PB15)") (class "Default")
      (node (ref "SPI1") (pin "3") (pinfunction "3_3") (pintype "passive"))
    )
    (net (code "74") (name "SPI2_NSS(PB12)") (class "Default")
      (node (ref "SPI1") (pin "1") (pinfunction "1_1") (pintype "passive"))
    )
    (net (code "75") (name "TIM1_CH1(PE9)") (class "Default")
      (node (ref "JP2") (pin "1") (pinfunction "1_1") (pintype "passive"))
    )
    (net (code "76") (name "TIM1_CH2(PE11)") (class "Default")
      (node (ref "JP4") (pin "1") (pinfunction "1_1") (pintype "passive"))
    )
    (net (code "77") (name "TIM1_CH3(PE13)") (class "Default")
      (node (ref "JP6") (pin "1") (pinfunction "1_1") (pintype "passive"))
    )
    (net (code "78") (name "TIM1_CH4(PE14)") (class "Default")
      (node (ref "JP8") (pin "1") (pinfunction "1_1") (pintype "passive"))
    )
    (net (code "79") (name "TIM2_CH1(PA15)") (class "Default")
      (node (ref "PWM_L1") (pin "1") (pinfunction "1_1") (pintype "passive"))
    )
    (net (code "80") (name "TIM2_CH2(PB3)") (class "Default")
      (node (ref "PWM_L1") (pin "4") (pinfunction "4_4") (pintype "passive"))
    )
    (net (code "81") (name "TIM2_CH3(PA2)") (class "Default")
      (node (ref "PWM_L1") (pin "7") (pinfunction "7_7") (pintype "passive"))
    )
    (net (code "82") (name "TIM2_CH4(PA3)") (class "Default")
      (node (ref "PWM_L1") (pin "10") (pinfunction "10_10") (pintype "passive"))
    )
    (net (code "83") (name "TIM4_CH1(PD12)") (class "Default")
      (node (ref "PWM_R1") (pin "3") (pinfunction "3_3") (pintype "passive"))
    )
    (net (code "84") (name "TIM4_CH2(PD13)") (class "Default")
      (node (ref "PWM_R1") (pin "6") (pinfunction "6_6") (pintype "passive"))
    )
    (net (code "85") (name "TIM4_CH3(PD14)") (class "Default")
      (node (ref "PWM_R1") (pin "9") (pinfunction "9_9") (pintype "passive"))
    )
    (net (code "86") (name "TIM4_CH4(PD15)") (class "Default")
      (node (ref "PWM_R1") (pin "12") (pinfunction "12_12") (pintype "passive"))
    )
    (net (code "87") (name "TIM5_CH1(PH10)") (class "Default")
      (node (ref "PWM_R1") (pin "15") (pinfunction "15_15") (pintype "passive"))
    )
    (net (code "88") (name "TIM5_CH2(PH11)") (class "Default")
      (node (ref "PWM_R1") (pin "18") (pinfunction "18_18") (pintype "passive"))
    )
    (net (code "89") (name "TIM5_CH3(PH12)") (class "Default")
      (node (ref "PWM_R1") (pin "21") (pinfunction "21_21") (pintype "passive"))
    )
    (net (code "90") (name "TIM5_CH4(PI0)") (class "Default")
      (node (ref "PWM_R1") (pin "24") (pinfunction "24_24") (pintype "passive"))
    )
    (net (code "91") (name "TIM8_CH1(PI5)") (class "Default")
      (node (ref "PWM_L1") (pin "13") (pinfunction "13_13") (pintype "passive"))
    )
    (net (code "92") (name "TIM8_CH2(PI6)") (class "Default")
      (node (ref "PWM_L1") (pin "16") (pinfunction "16_16") (pintype "passive"))
    )
    (net (code "93") (name "TIM8_CH3(PI7)") (class "Default")
      (node (ref "PWM_L1") (pin "19") (pinfunction "19_19") (pintype "passive"))
    )
    (net (code "94") (name "TIM8_CH4(PI2)") (class "Default")
      (node (ref "PWM_L1") (pin "22") (pinfunction "22_22") (pintype "passive"))
    )
    (net (code "95") (name "TIM10_CH1(PF6)") (class "Default")
      (node (ref "R14") (pin "1") (pinfunction "1_1") (pintype "passive"))
    )
    (net (code "96") (name "TIM11_CH1(PF7)") (class "Default")
      (node (ref "Q5") (pin "2") (pinfunction "S_2") (pintype "passive"))
      (node (ref "R39") (pin "2") (pinfunction "2_2") (pintype "passive"))
    )
    (net (code "97") (name "TIM13_CH1(PF8)") (class "Default")
      (node (ref "Q6") (pin "2") (pinfunction "S_2") (pintype "passive"))
      (node (ref "R41") (pin "2") (pinfunction "2_2") (pintype "passive"))
    )
    (net (code "98") (name "TIM14_CH1(PF9)") (class "Default")
      (node (ref "Q4") (pin "2") (pinfunction "S_2") (pintype "passive"))
      (node (ref "R38") (pin "2") (pinfunction "2_2") (pintype "passive"))
    )
    (net (code "99") (name "UART4_RX(PA1)") (class "Default")
      (node (ref "Q3") (pin "3") (pinfunction "C_3") (pintype "passive"))
      (node (ref "R11") (pin "1") (pinfunction "1_1") (pintype "passive"))
    )
    (net (code "100") (name "USART1_RX(PA10)") (class "Default")
      (node (ref "USART1") (pin "2") (pinfunction "2_2") (pintype "passive"))
    )
    (net (code "101") (name "USART1_TX(PA9)") (class "Default")
      (node (ref "USART1") (pin "1") (pinfunction "1_1") (pintype "passive"))
    )
    (net (code "102") (name "USART2_RX(PD6)") (class "Default")
      (node (ref "USART2") (pin "2") (pinfunction "2_2") (pintype "passive"))
    )
    (net (code "103") (name "USART2_TX(PD5)") (class "Default")
      (node (ref "USART2") (pin "1") (pinfunction "1_1") (pintype "passive"))
    )
    (net (code "104") (name "USART3_RX(PD9)") (class "Default")
      (node (ref "USART3") (pin "2") (pinfunction "2_2") (pintype "passive"))
    )
    (net (code "105") (name "USART3_TX(PD8)") (class "Default")
      (node (ref "USART3") (pin "1") (pinfunction "1_1") (pintype "passive"))
    )
    (net (code "106") (name "USART6_RX(PC7)") (class "Default")
      (node (ref "USART4") (pin "2") (pinfunction "2_2") (pintype "passive"))
    )
    (net (code "107") (name "USART6_TX(PC6)") (class "Default")
      (node (ref "USART4") (pin "1") (pinfunction "1_1") (pintype "passive"))
    )
    (net (code "108") (name "USB_DM(PA11)") (class "Default")
      (node (ref "R33") (pin "1") (pinfunction "1_1") (pintype "passive"))
    )
    (net (code "109") (name "USB_DP(PA12)") (class "Default")
      (node (ref "R34") (pin "1") (pinfunction "1_1") (pintype "passive"))
    )
    (net (code "110") (name "VBUS") (class "Default")
      (node (ref "C27") (pin "2") (pinfunction "2_2") (pintype "passive"))
      (node (ref "C28") (pin "2") (pinfunction "2_2") (pintype "passive"))
      (node (ref "J1") (pin "3") (pinfunction "VCC_3") (pintype "passive"))
      (node (ref "J2") (pin "3") (pinfunction "VCC_3") (pintype "passive"))
      (node (ref "USB1") (pin "A4") (pinfunction "VBUS_A4") (pintype "passive"))
      (node (ref "USB1") (pin "B9") (pinfunction "VBUS_B9") (pintype "passive"))
    )
    (net (code "111") (name "VCC3V3") (class "Default")
      (node (ref "Q4") (pin "1") (pinfunction "G_1") (pintype "passive"))
      (node (ref "Q5") (pin "1") (pinfunction "G_1") (pintype "passive"))
      (node (ref "Q6") (pin "1") (pinfunction "G_1") (pintype "passive"))
      (node (ref "R38") (pin "1") (pinfunction "1_1") (pintype "passive"))
      (node (ref "R39") (pin "1") (pinfunction "1_1") (pintype "passive"))
      (node (ref "R41") (pin "1") (pinfunction "1_1") (pintype "passive"))
    )
    (net (code "112") (name "VCC5V") (class "Default")
      (node (ref "C26") (pin "1") (pinfunction "1_1") (pintype "passive"))
      (node (ref "CAN2") (pin "4") (pinfunction "4_4") (pintype "passive"))
      (node (ref "CAN8") (pin "4") (pinfunction "4_4") (pintype "passive"))
      (node (ref "D1") (pin "2") (pinfunction "K_2") (pintype "passive"))
      (node (ref "DBUS1") (pin "2") (pinfunction "2_2") (pintype "passive"))
      (node (ref "IC1") (pin "3") (pinfunction "VDD_3") (pintype "passive"))
      (node (ref "IIC1") (pin "4") (pinfunction "4_4") (pintype "passive"))
      (node (ref "IIC2") (pin "4") (pinfunction "4_4") (pintype "passive"))
      (node (ref "IIC3") (pin "4") (pinfunction "4_4") (pintype "passive"))
      (node (ref "LASER1") (pin "1") (pinfunction "1_1") (pintype "passive"))
      (node (ref "LS1") (pin "1") (pinfunction "1_1") (pintype "passive"))
      (node (ref "R36") (pin "1") (pinfunction "1_1") (pintype "passive"))
      (node (ref "R37") (pin "1") (pinfunction "1_1") (pintype "passive"))
      (node (ref "R40") (pin "1") (pinfunction "1_1") (pintype "passive"))
      (node (ref "SPI1") (pin "5") (pinfunction "5_5") (pintype "passive"))
      (node (ref "USART1") (pin "4") (pinfunction "4_4") (pintype "passive"))
      (node (ref "USART2") (pin "4") (pinfunction "4_4") (pintype "passive"))
      (node (ref "USART3") (pin "4") (pinfunction "4_4") (pintype "passive"))
      (node (ref "USART4") (pin "4") (pinfunction "4_4") (pintype "passive"))
    )
    (net (code "113") (name "VCC_3V3") (class "Default")
      (node (ref "C29") (pin "2") (pinfunction "2_2") (pintype "passive"))
      (node (ref "OLED1") (pin "1") (pinfunction "1_1") (pintype "passive"))
      (node (ref "R11") (pin "2") (pinfunction "2_2") (pintype "passive"))
      (node (ref "R19") (pin "1") (pinfunction "1_1") (pintype "passive"))
      (node (ref "R20") (pin "1") (pinfunction "1_1") (pintype "passive"))
      (node (ref "R21") (pin "1") (pinfunction "1_1") (pintype "passive"))
      (node (ref "R22") (pin "1") (pinfunction "1_1") (pintype "passive"))
      (node (ref "R23") (pin "1") (pinfunction "1_1") (pintype "passive"))
      (node (ref "R24") (pin "1") (pinfunction "1_1") (pintype "passive"))
      (node (ref "R25") (pin "1") (pinfunction "1_1") (pintype "passive"))
      (node (ref "R26") (pin "1") (pinfunction "1_1") (pintype "passive"))
      (node (ref "R27") (pin "1") (pinfunction "1_1") (pintype "passive"))
      (node (ref "R28") (pin "1") (pinfunction "1_1") (pintype "passive"))
      (node (ref "R29") (pin "1") (pinfunction "1_1") (pintype "passive"))
      (node (ref "R30") (pin "1") (pinfunction "1_1") (pintype "passive"))
      (node (ref "R31") (pin "1") (pinfunction "1_1") (pintype "passive"))
      (node (ref "R32") (pin "1") (pinfunction "1_1") (pintype "passive"))
      (node (ref "R35") (pin "1") (pinfunction "1_1") (pintype "passive"))
      (node (ref "RST2") (pin "1") (pinfunction "1_1") (pintype "passive"))
      (node (ref "RST3") (pin "1") (pinfunction "1_1") (pintype "passive"))
      (node (ref "TF_Card1") (pin "4") (pinfunction "VDD_4") (pintype "passive"))
    )
    (net (code "114") (name "VCC_PWM") (class "Default")
      (node (ref "JP1") (pin "2") (pinfunction "2_2") (pintype "passive"))
      (node (ref "JP2") (pin "2") (pinfunction "2_2") (pintype "passive"))
      (node (ref "JP3") (pin "2") (pinfunction "2_2") (pintype "passive"))
      (node (ref "JP4") (pin "2") (pinfunction "2_2") (pintype "passive"))
      (node (ref "JP5") (pin "2") (pinfunction "2_2") (pintype "passive"))
      (node (ref "JP6") (pin "2") (pinfunction "2_2") (pintype "passive"))
      (node (ref "JP7") (pin "2") (pinfunction "2_2") (pintype "passive"))
      (node (ref "JP8") (pin "2") (pinfunction "2_2") (pintype "passive"))
      (node (ref "PWM_L1") (pin "11") (pinfunction "11_11") (pintype "passive"))
      (node (ref "PWM_L1") (pin "14") (pinfunction "14_14") (pintype "passive"))
      (node (ref "PWM_L1") (pin "17") (pinfunction "17_17") (pintype "passive"))
      (node (ref "PWM_L1") (pin "2") (pinfunction "2_2") (pintype "passive"))
      (node (ref "PWM_L1") (pin "20") (pinfunction "20_20") (pintype "passive"))
      (node (ref "PWM_L1") (pin "23") (pinfunction "23_23") (pintype "passive"))
      (node (ref "PWM_L1") (pin "5") (pinfunction "5_5") (pintype "passive"))
      (node (ref "PWM_L1") (pin "8") (pinfunction "8_8") (pintype "passive"))
      (node (ref "PWM_R1") (pin "11") (pinfunction "11_11") (pintype "passive"))
      (node (ref "PWM_R1") (pin "14") (pinfunction "14_14") (pintype "passive"))
      (node (ref "PWM_R1") (pin "17") (pinfunction "17_17") (pintype "passive"))
      (node (ref "PWM_R1") (pin "2") (pinfunction "2_2") (pintype "passive"))
      (node (ref "PWM_R1") (pin "20") (pinfunction "20_20") (pintype "passive"))
      (node (ref "PWM_R1") (pin "23") (pinfunction "23_23") (pintype "passive"))
      (node (ref "PWM_R1") (pin "5") (pinfunction "5_5") (pintype "passive"))
      (node (ref "PWM_R1") (pin "8") (pinfunction "8_8") (pintype "passive"))
    )
    (net (code "115") (name "unconnected-(IC1-DOUT-Pad4)") (class "Default")
      (node (ref "IC1") (pin "4") (pinfunction "DOUT_4") (pintype "passive+no_connect"))
    )
    (net (code "116") (name "unconnected-(J1-Vref-Pad5)") (class "Default")
      (node (ref "J1") (pin "5") (pinfunction "Vref_5") (pintype "passive+no_connect"))
    )
    (net (code "117") (name "unconnected-(J2-Vref-Pad5)") (class "Default")
      (node (ref "J2") (pin "5") (pinfunction "Vref_5") (pintype "passive+no_connect"))
    )
    (net (code "118") (name "unconnected-(LS1-Pad3)") (class "Default")
      (node (ref "LS1") (pin "3") (pinfunction "3_3") (pintype "passive+no_connect"))
    )
    (net (code "119") (name "unconnected-(TF_Card1-K-Pad9)") (class "Default")
      (node (ref "TF_Card1") (pin "9") (pinfunction "K_9") (pintype "passive+no_connect"))
    )
    (net (code "120") (name "unconnected-(USB1-CC1-PadA5)") (class "Default")
      (node (ref "USB1") (pin "A5") (pinfunction "CC1_A5") (pintype "passive"))
    )
    (net (code "121") (name "unconnected-(USB1-CC2-PadB5)") (class "Default")
      (node (ref "USB1") (pin "B5") (pinfunction "CC2_B5") (pintype "passive"))
    )
    (net (code "122") (name "unconnected-(USB1-RX1+-PadB11)") (class "Default")
      (node (ref "USB1") (pin "B11") (pinfunction "RX1+_B11") (pintype "passive"))
    )
    (net (code "123") (name "unconnected-(USB1-RX1--PadB10)") (class "Default")
      (node (ref "USB1") (pin "B10") (pinfunction "RX1-_B10") (pintype "passive"))
    )
    (net (code "124") (name "unconnected-(USB1-RX2+-PadA11)") (class "Default")
      (node (ref "USB1") (pin "A11") (pinfunction "RX2+_A11") (pintype "passive"))
    )
    (net (code "125") (name "unconnected-(USB1-RX2--PadA10)") (class "Default")
      (node (ref "USB1") (pin "A10") (pinfunction "RX2-_A10") (pintype "passive"))
    )
    (net (code "126") (name "unconnected-(USB1-SBU1-PadA8)") (class "Default")
      (node (ref "USB1") (pin "A8") (pinfunction "SBU1_A8") (pintype "passive"))
    )
    (net (code "127") (name "unconnected-(USB1-SBU2-PadB8)") (class "Default")
      (node (ref "USB1") (pin "B8") (pinfunction "SBU2_B8") (pintype "passive"))
    )
    (net (code "128") (name "unconnected-(USB1-SH1-Pad1)") (class "Default")
      (node (ref "USB1") (pin "1") (pinfunction "SH1_1") (pintype "passive"))
    )
    (net (code "129") (name "unconnected-(USB1-SH2-Pad2)") (class "Default")
      (node (ref "USB1") (pin "2") (pinfunction "SH2_2") (pintype "passive"))
    )
    (net (code "130") (name "unconnected-(USB1-SH3-Pad3)") (class "Default")
      (node (ref "USB1") (pin "3") (pinfunction "SH3_3") (pintype "passive"))
    )
    (net (code "131") (name "unconnected-(USB1-SH4-Pad4)") (class "Default")
      (node (ref "USB1") (pin "4") (pinfunction "SH4_4") (pintype "passive"))
    )
    (net (code "132") (name "unconnected-(USB1-TX1+-PadA2)") (class "Default")
      (node (ref "USB1") (pin "A2") (pinfunction "TX1+_A2") (pintype "passive"))
    )
    (net (code "133") (name "unconnected-(USB1-TX1--PadA3)") (class "Default")
      (node (ref "USB1") (pin "A3") (pinfunction "TX1-_A3") (pintype "passive"))
    )
    (net (code "134") (name "unconnected-(USB1-TX2+-PadB2)") (class "Default")
      (node (ref "USB1") (pin "B2") (pinfunction "TX2+_B2") (pintype "passive"))
    )
    (net (code "135") (name "unconnected-(USB1-TX2--PadB3)") (class "Default")
      (node (ref "USB1") (pin "B3") (pinfunction "TX2-_B3") (pintype "passive"))
    )
    (net (code "136") (name "unconnected-(USB1-VBUS-PadA9)") (class "Default")
      (node (ref "USB1") (pin "A9") (pinfunction "VBUS_A9") (pintype "passive"))
    )
    (net (code "137") (name "unconnected-(USB1-VBUS-PadB4)") (class "Default")
      (node (ref "USB1") (pin "B4") (pinfunction "VBUS_B4") (pintype "passive"))
    )
  )
)
